# design.net
KiCad netlist of a schematic drawn in Altium Designer
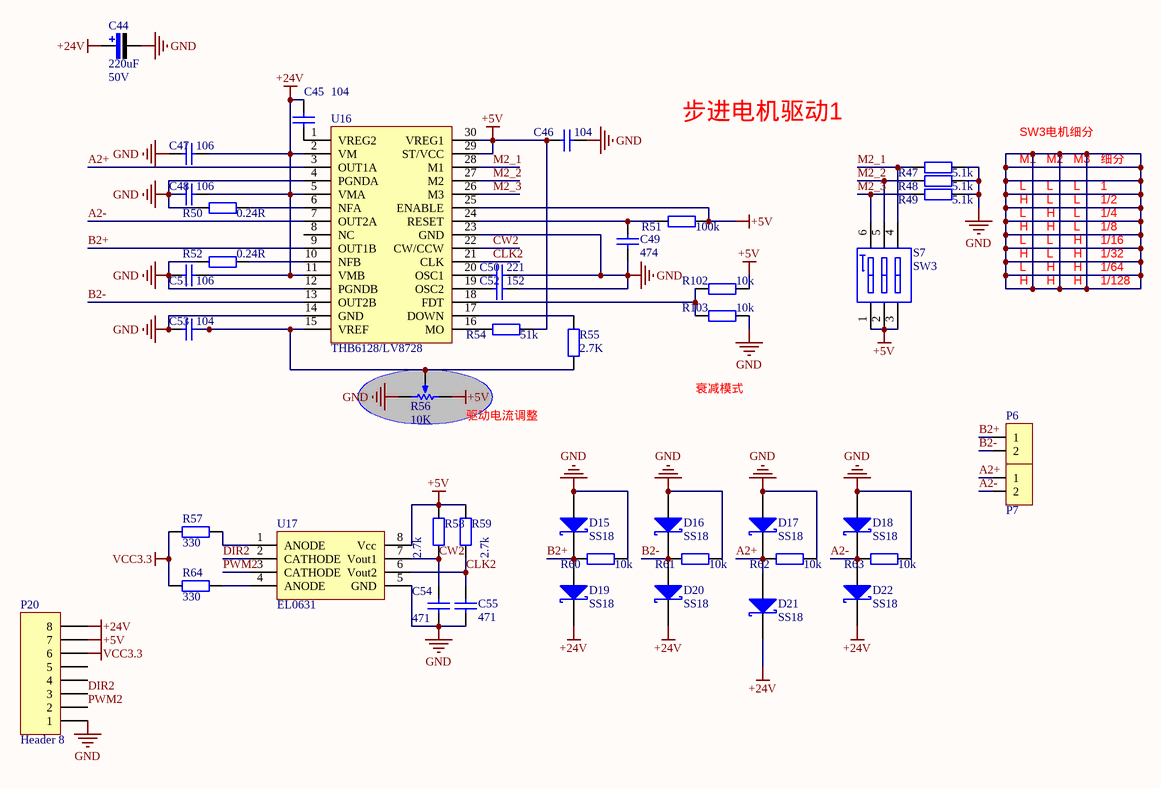
[diagram p0: 升降电机驱动.SchDoc]

(export (version "E")
  (design (tool "Eeschema 10.0.6"))
  (components
    (comp (ref "C44")
      (value "220uF")
      (footprint "C-RB-S10")
      (description "极性电解电容")
      (fields
        (field (name "VOL") "50V")
        (field (name "Comment") "Cap Pol")
        (field (name "PUBLISHER") "Altium Limited")
      )
      (libsource (lib "Fszhang") (part "Cap Pol"))
    )
    (comp (ref "C45")
      (value "104")
      (footprint "C-RAD-0603")
      (description "无极性电容")
      (fields (field (name "Comment") "Cap") (field (name "PUBLISHER") "Altium Limited"))
      (libsource (lib "Fszhang") (part "Cap"))
    )
    (comp (ref "C46")
      (value "104")
      (footprint "C-RAD-0603")
      (description "无极性电容")
      (fields (field (name "Comment") "Cap") (field (name "PUBLISHER") "Altium Limited"))
      (libsource (lib "Fszhang") (part "Cap"))
    )
    (comp (ref "C47")
      (value "106")
      (footprint "C-RAD-0603")
      (description "无极性电容")
      (fields (field (name "Comment") "Cap") (field (name "PUBLISHER") "Altium Limited"))
      (libsource (lib "Fszhang") (part "Cap"))
    )
    (comp (ref "C48")
      (value "106")
      (footprint "C-RAD-0603")
      (description "无极性电容")
      (fields (field (name "Comment") "Cap") (field (name "PUBLISHER") "Altium Limited"))
      (libsource (lib "Fszhang") (part "Cap"))
    )
    (comp (ref "C49")
      (value "474")
      (footprint "C-RAD-0603")
      (description "无极性电容")
      (fields (field (name "Comment") "Cap") (field (name "PUBLISHER") "Altium Limited"))
      (libsource (lib "Fszhang") (part "Cap"))
    )
    (comp (ref "C50")
      (value "221")
      (footprint "C-RAD-0603")
      (description "无极性电容")
      (fields (field (name "Comment") "Cap") (field (name "PUBLISHER") "Altium Limited"))
      (libsource (lib "Fszhang") (part "Cap"))
    )
    (comp (ref "C51")
      (value "106")
      (footprint "C-RAD-0603")
      (description "无极性电容")
      (fields (field (name "Comment") "Cap") (field (name "PUBLISHER") "Altium Limited"))
      (libsource (lib "Fszhang") (part "Cap"))
    )
    (comp (ref "C52")
      (value "152")
      (footprint "C-RAD-0603")
      (description "无极性电容")
      (fields (field (name "Comment") "Cap") (field (name "PUBLISHER") "Altium Limited"))
      (libsource (lib "Fszhang") (part "Cap"))
    )
    (comp (ref "C53")
      (value "104")
      (footprint "C-RAD-0603")
      (description "无极性电容")
      (fields (field (name "Comment") "Cap") (field (name "PUBLISHER") "Altium Limited"))
      (libsource (lib "Fszhang") (part "Cap"))
    )
    (comp (ref "C54")
      (value "471")
      (footprint "C-RAD-0603")
      (description "无极性电容")
      (fields (field (name "Comment") "Cap") (field (name "PUBLISHER") "Altium Limited"))
      (libsource (lib "Fszhang") (part "Cap"))
    )
    (comp (ref "C55")
      (value "471")
      (footprint "C-RAD-0603")
      (description "无极性电容")
      (fields (field (name "Comment") "Cap") (field (name "PUBLISHER") "Altium Limited"))
      (libsource (lib "Fszhang") (part "Cap"))
    )
    (comp (ref "D15")
      (value "D-Schottky")
      (footprint "DIODE-SMA")
      (description "肖特基二极管")
      (fields (field (name "TYPE") "SS18") (field (name "PUBLISHER") "Altium Limited"))
      (libsource (lib "Fszhang") (part "D-Schottky"))
    )
    (comp (ref "D16")
      (value "D-Schottky")
      (footprint "DIODE-SMA")
      (description "肖特基二极管")
      (fields (field (name "TYPE") "SS18") (field (name "PUBLISHER") "Altium Limited"))
      (libsource (lib "Fszhang") (part "D-Schottky"))
    )
    (comp (ref "D17")
      (value "D-Schottky")
      (footprint "DIODE-SMA")
      (description "肖特基二极管")
      (fields (field (name "TYPE") "SS18") (field (name "PUBLISHER") "Altium Limited"))
      (libsource (lib "Fszhang") (part "D-Schottky"))
    )
    (comp (ref "D18")
      (value "D-Schottky")
      (footprint "DIODE-SMA")
      (description "肖特基二极管")
      (fields (field (name "TYPE") "SS18") (field (name "PUBLISHER") "Altium Limited"))
      (libsource (lib "Fszhang") (part "D-Schottky"))
    )
    (comp (ref "D19")
      (value "D-Schottky")
      (footprint "DIODE-SMA")
      (description "肖特基二极管")
      (fields (field (name "TYPE") "SS18") (field (name "PUBLISHER") "Altium Limited"))
      (libsource (lib "Fszhang") (part "D-Schottky"))
    )
    (comp (ref "D20")
      (value "D-Schottky")
      (footprint "DIODE-SMA")
      (description "肖特基二极管")
      (fields (field (name "TYPE") "SS18") (field (name "PUBLISHER") "Altium Limited"))
      (libsource (lib "Fszhang") (part "D-Schottky"))
    )
    (comp (ref "D21")
      (value "D-Schottky")
      (footprint "DIODE-SMA")
      (description "肖特基二极管")
      (fields (field (name "TYPE") "SS18") (field (name "PUBLISHER") "Altium Limited"))
      (libsource (lib "Fszhang") (part "D-Schottky"))
    )
    (comp (ref "D22")
      (value "D-Schottky")
      (footprint "DIODE-SMA")
      (description "肖特基二极管")
      (fields (field (name "TYPE") "SS18") (field (name "PUBLISHER") "Altium Limited"))
      (libsource (lib "Fszhang") (part "D-Schottky"))
    )
    (comp (ref "P6") (value "cnt2p") (footprint "接线端子5mm间距2p") (libsource (lib "MY_Library") (part "cnt2p")))
    (comp (ref "P7") (value "cnt2p") (footprint "接线端子5mm间距2p") (libsource (lib "MY_Library") (part "cnt2p")))
    (comp (ref "P20")
      (value "Header 8")
      (footprint "PH2.0-8P")
      (description "Header, 8-Pin")
      (fields (field (name "PUBLISHER") "Altium Limited"))
      (libsource (lib "Fszhang") (part "Header 8"))
    )
    (comp (ref "R47")
      (value "5.1k")
      (footprint "0603-1")
      (description "贴片电阻")
      (fields (field (name "Comment") "Res1") (field (name "PUBLISHER") "Altium Limited"))
      (libsource (lib "Fszhang") (part "Res1"))
    )
    (comp (ref "R48")
      (value "5.1k")
      (footprint "0603-1")
      (description "贴片电阻")
      (fields (field (name "Comment") "Res1") (field (name "PUBLISHER") "Altium Limited"))
      (libsource (lib "Fszhang") (part "Res1"))
    )
    (comp (ref "R49")
      (value "5.1k")
      (footprint "0603-1")
      (description "贴片电阻")
      (fields (field (name "Comment") "Res1") (field (name "PUBLISHER") "Altium Limited"))
      (libsource (lib "Fszhang") (part "Res1"))
    )
    (comp (ref "R50")
      (value "0.24R")
      (footprint "2512")
      (description "贴片电阻")
      (fields (field (name "Comment") "Res1") (field (name "PUBLISHER") "Altium Limited"))
      (libsource (lib "Fszhang") (part "Res1"))
    )
    (comp (ref "R51")
      (value "100k")
      (footprint "0603-1")
      (description "贴片电阻")
      (fields (field (name "Comment") "Res1") (field (name "PUBLISHER") "Altium Limited"))
      (libsource (lib "Fszhang") (part "Res1"))
    )
    (comp (ref "R52")
      (value "0.24R")
      (footprint "2512")
      (description "贴片电阻")
      (fields (field (name "Comment") "Res1") (field (name "PUBLISHER") "Altium Limited"))
      (libsource (lib "") (part "Res1_2"))
    )
    (comp (ref "R54")
      (value "51k")
      (footprint "0603-1")
      (description "贴片电阻")
      (fields (field (name "Comment") "Res1") (field (name "PUBLISHER") "Altium Limited"))
      (libsource (lib "Fszhang") (part "Res1"))
    )
    (comp (ref "R55")
      (value "2.7K")
      (footprint "0603-1")
      (description "贴片电阻")
      (fields (field (name "Comment") "Res1") (field (name "PUBLISHER") "Altium Limited"))
      (libsource (lib "") (part "Res1_3"))
    )
    (comp (ref "R56")
      (value "10K")
      (footprint "VR-3266W")
      (description "精密可调电阻")
      (fields (field (name "Comment") "RPot") (field (name "PUBLISHER") "Altium Limited"))
      (libsource (lib "Fszhang") (part "RPot"))
    )
    (comp (ref "R57")
      (value "330")
      (footprint "0603-1")
      (description "贴片电阻")
      (fields (field (name "Comment") "Res1") (field (name "PUBLISHER") "Altium Limited"))
      (libsource (lib "") (part "Res1_2"))
    )
    (comp (ref "R58")
      (value "2.7k")
      (footprint "0603-1")
      (description "贴片电阻")
      (fields (field (name "Comment") "Res1") (field (name "PUBLISHER") "Altium Limited"))
      (libsource (lib "") (part "Res1_1"))
    )
    (comp (ref "R59")
      (value "2.7k")
      (footprint "0603-1")
      (description "贴片电阻")
      (fields (field (name "Comment") "Res1") (field (name "PUBLISHER") "Altium Limited"))
      (libsource (lib "") (part "Res1_1"))
    )
    (comp (ref "R60")
      (value "10k")
      (footprint "0603-1")
      (description "贴片电阻")
      (fields (field (name "Comment") "Res1") (field (name "PUBLISHER") "Altium Limited"))
      (libsource (lib "Fszhang") (part "Res1"))
    )
    (comp (ref "R61")
      (value "10k")
      (footprint "0603-1")
      (description "贴片电阻")
      (fields (field (name "Comment") "Res1") (field (name "PUBLISHER") "Altium Limited"))
      (libsource (lib "Fszhang") (part "Res1"))
    )
    (comp (ref "R62")
      (value "10k")
      (footprint "0603-1")
      (description "贴片电阻")
      (fields (field (name "Comment") "Res1") (field (name "PUBLISHER") "Altium Limited"))
      (libsource (lib "Fszhang") (part "Res1"))
    )
    (comp (ref "R63")
      (value "10k")
      (footprint "0603-1")
      (description "贴片电阻")
      (fields (field (name "Comment") "Res1") (field (name "PUBLISHER") "Altium Limited"))
      (libsource (lib "Fszhang") (part "Res1"))
    )
    (comp (ref "R64")
      (value "330")
      (footprint "0603-1")
      (description "贴片电阻")
      (fields (field (name "Comment") "Res1") (field (name "PUBLISHER") "Altium Limited"))
      (libsource (lib "") (part "Res1_2"))
    )
    (comp (ref "R102")
      (value "10k")
      (footprint "0603-1")
      (description "贴片电阻")
      (fields (field (name "Comment") "Res1") (field (name "PUBLISHER") "Altium Limited"))
      (libsource (lib "Fszhang") (part "Res1"))
    )
    (comp (ref "R103")
      (value "10k")
      (footprint "0603-1")
      (description "贴片电阻")
      (fields (field (name "Comment") "Res1") (field (name "PUBLISHER") "Altium Limited"))
      (libsource (lib "Fszhang") (part "Res1"))
    )
    (comp (ref "S7")
      (value "SW3")
      (footprint "SW6_3BIT")
      (description "3位编码开关")
      (libsource (lib "Fszhang") (part "SW3"))
    )
    (comp (ref "U16")
      (value "THB6128/LV8728")
      (footprint "SIOC-30-W")
      (description "步进电机驱动")
      (libsource (lib "Fszhang") (part "THB6128"))
    )
    (comp (ref "U17")
      (value "EL0631")
      (footprint "EL0631")
      (description "双路隔离光耦")
      (libsource (lib "Fszhang") (part "EL0631"))
    )
  )
  (nets
    (net (code "1") (name "+5V") (class "Default")
      (node (ref "C46") (pin "1") (pinfunction "1_1") (pintype "passive"))
      (node (ref "P20") (pin "7") (pinfunction "7_7") (pintype "passive"))
      (node (ref "R102") (pin "2") (pinfunction "2_2") (pintype "passive"))
      (node (ref "R51") (pin "2") (pinfunction "2_2") (pintype "passive"))
      (node (ref "R54") (pin "2") (pinfunction "2_2") (pintype "passive"))
      (node (ref "R56") (pin "1") (pinfunction "TOP_1") (pintype "passive"))
      (node (ref "R58") (pin "2") (pinfunction "2_2") (pintype "passive"))
      (node (ref "R59") (pin "2") (pinfunction "2_2") (pintype "passive"))
      (node (ref "S7") (pin "1") (pinfunction "1_1") (pintype "passive"))
      (node (ref "S7") (pin "2") (pinfunction "2_2") (pintype "passive"))
      (node (ref "S7") (pin "3") (pinfunction "3_3") (pintype "passive"))
      (node (ref "U16") (pin "25") (pinfunction "ENABLE_25") (pintype "passive"))
      (node (ref "U16") (pin "29") (pinfunction "ST/VCC_29") (pintype "passive"))
      (node (ref "U16") (pin "30") (pinfunction "VREG1_30") (pintype "passive"))
      (node (ref "U17") (pin "8") (pinfunction "Vcc_8") (pintype "passive"))
    )
    (net (code "2") (name "+24V") (class "Default")
      (node (ref "C44") (pin "1") (pinfunction "1_1") (pintype "passive"))
      (node (ref "C45") (pin "1") (pinfunction "1_1") (pintype "passive"))
      (node (ref "C47") (pin "2") (pinfunction "2_2") (pintype "passive"))
      (node (ref "C48") (pin "2") (pinfunction "2_2") (pintype "passive"))
      (node (ref "C51") (pin "2") (pinfunction "2_2") (pintype "passive"))
      (node (ref "D19") (pin "2") (pinfunction "K_2") (pintype "passive"))
      (node (ref "D20") (pin "2") (pinfunction "K_2") (pintype "passive"))
      (node (ref "D21") (pin "2") (pinfunction "K_2") (pintype "passive"))
      (node (ref "D22") (pin "2") (pinfunction "K_2") (pintype "passive"))
      (node (ref "P20") (pin "8") (pinfunction "8_8") (pintype "passive"))
      (node (ref "U16") (pin "11") (pinfunction "VMB_11") (pintype "passive"))
      (node (ref "U16") (pin "2") (pinfunction "VM_2") (pintype "passive"))
      (node (ref "U16") (pin "5") (pinfunction "VMA_5") (pintype "passive"))
    )
    (net (code "3") (name "/A2+") (class "Default")
      (node (ref "D17") (pin "2") (pinfunction "K_2") (pintype "passive"))
      (node (ref "D21") (pin "1") (pinfunction "A_1") (pintype "passive"))
      (node (ref "P7") (pin "1") (pinfunction "1_1") (pintype "passive"))
      (node (ref "R62") (pin "1") (pinfunction "1_1") (pintype "passive"))
      (node (ref "U16") (pin "3") (pinfunction "OUT1A_3") (pintype "passive"))
    )
    (net (code "4") (name "/A2-") (class "Default")
      (node (ref "D18") (pin "2") (pinfunction "K_2") (pintype "passive"))
      (node (ref "D22") (pin "1") (pinfunction "A_1") (pintype "passive"))
      (node (ref "P7") (pin "2") (pinfunction "2_2") (pintype "passive"))
      (node (ref "R63") (pin "1") (pinfunction "1_1") (pintype "passive"))
      (node (ref "U16") (pin "7") (pinfunction "OUT2A_7") (pintype "passive"))
    )
    (net (code "5") (name "/B2+") (class "Default")
      (node (ref "D15") (pin "2") (pinfunction "K_2") (pintype "passive"))
      (node (ref "D19") (pin "1") (pinfunction "A_1") (pintype "passive"))
      (node (ref "P6") (pin "1") (pinfunction "1_1") (pintype "passive"))
      (node (ref "R60") (pin "1") (pinfunction "1_1") (pintype "passive"))
      (node (ref "U16") (pin "9") (pinfunction "OUT1B_9") (pintype "passive"))
    )
    (net (code "6") (name "/B2-") (class "Default")
      (node (ref "D16") (pin "2") (pinfunction "K_2") (pintype "passive"))
      (node (ref "D20") (pin "1") (pinfunction "A_1") (pintype "passive"))
      (node (ref "P6") (pin "2") (pinfunction "2_2") (pintype "passive"))
      (node (ref "R61") (pin "1") (pinfunction "1_1") (pintype "passive"))
      (node (ref "U16") (pin "13") (pinfunction "OUT2B_13") (pintype "passive"))
    )
    (net (code "7") (name "/CLK2") (class "Default")
      (node (ref "C55") (pin "2") (pinfunction "2_2") (pintype "passive"))
      (node (ref "R59") (pin "1") (pinfunction "1_1") (pintype "passive"))
      (node (ref "U16") (pin "21") (pinfunction "CLK_21") (pintype "passive"))
      (node (ref "U17") (pin "6") (pinfunction "Vout2_6") (pintype "passive"))
    )
    (net (code "8") (name "/CW2") (class "Default")
      (node (ref "C54") (pin "2") (pinfunction "2_2") (pintype "passive"))
      (node (ref "R58") (pin "1") (pinfunction "1_1") (pintype "passive"))
      (node (ref "U16") (pin "22") (pinfunction "CW/CCW_22") (pintype "passive"))
      (node (ref "U17") (pin "7") (pinfunction "Vout1_7") (pintype "passive"))
    )
    (net (code "9") (name "/DIR2") (class "Default")
      (node (ref "P20") (pin "3") (pinfunction "3_3") (pintype "passive"))
      (node (ref "U17") (pin "2") (pinfunction "CATHODE_2") (pintype "passive"))
    )
    (net (code "10") (name "/M2_1") (class "Default")
      (node (ref "R47") (pin "1") (pinfunction "1_1") (pintype "passive"))
      (node (ref "S7") (pin "4") (pinfunction "4_4") (pintype "passive"))
      (node (ref "U16") (pin "28") (pinfunction "M1_28") (pintype "passive"))
    )
    (net (code "11") (name "/M2_2") (class "Default")
      (node (ref "R48") (pin "1") (pinfunction "1_1") (pintype "passive"))
      (node (ref "S7") (pin "5") (pinfunction "5_5") (pintype "passive"))
      (node (ref "U16") (pin "27") (pinfunction "M2_27") (pintype "passive"))
    )
    (net (code "12") (name "/M2_3") (class "Default")
      (node (ref "R49") (pin "1") (pinfunction "1_1") (pintype "passive"))
      (node (ref "S7") (pin "6") (pinfunction "6_6") (pintype "passive"))
      (node (ref "U16") (pin "26") (pinfunction "M3_26") (pintype "passive"))
    )
    (net (code "13") (name "/PWM2") (class "Default")
      (node (ref "P20") (pin "2") (pinfunction "2_2") (pintype "passive"))
      (node (ref "U17") (pin "3") (pinfunction "CATHODE_3") (pintype "passive"))
    )
    (net (code "14") (name "GND") (class "Default")
      (node (ref "C44") (pin "2") (pinfunction "2_2") (pintype "passive"))
      (node (ref "C46") (pin "2") (pinfunction "2_2") (pintype "passive"))
      (node (ref "C47") (pin "1") (pinfunction "1_1") (pintype "passive"))
      (node (ref "C48") (pin "1") (pinfunction "1_1") (pintype "passive"))
      (node (ref "C49") (pin "1") (pinfunction "1_1") (pintype "passive"))
      (node (ref "C50") (pin "2") (pinfunction "2_2") (pintype "passive"))
      (node (ref "C51") (pin "1") (pinfunction "1_1") (pintype "passive"))
      (node (ref "C52") (pin "2") (pinfunction "2_2") (pintype "passive"))
      (node (ref "C53") (pin "1") (pinfunction "1_1") (pintype "passive"))
      (node (ref "C54") (pin "1") (pinfunction "1_1") (pintype "passive"))
      (node (ref "C55") (pin "1") (pinfunction "1_1") (pintype "passive"))
      (node (ref "D15") (pin "1") (pinfunction "A_1") (pintype "passive"))
      (node (ref "D16") (pin "1") (pinfunction "A_1") (pintype "passive"))
      (node (ref "D17") (pin "1") (pinfunction "A_1") (pintype "passive"))
      (node (ref "D18") (pin "1") (pinfunction "A_1") (pintype "passive"))
      (node (ref "P20") (pin "1") (pinfunction "1_1") (pintype "passive"))
      (node (ref "R103") (pin "2") (pinfunction "2_2") (pintype "passive"))
      (node (ref "R47") (pin "2") (pinfunction "2_2") (pintype "passive"))
      (node (ref "R48") (pin "2") (pinfunction "2_2") (pintype "passive"))
      (node (ref "R49") (pin "2") (pinfunction "2_2") (pintype "passive"))
      (node (ref "R50") (pin "1") (pinfunction "1_1") (pintype "passive"))
      (node (ref "R52") (pin "2") (pinfunction "2_2") (pintype "passive"))
      (node (ref "R56") (pin "3") (pinfunction "BOT_3") (pintype "passive"))
      (node (ref "R60") (pin "2") (pinfunction "2_2") (pintype "passive"))
      (node (ref "R61") (pin "2") (pinfunction "2_2") (pintype "passive"))
      (node (ref "R62") (pin "2") (pinfunction "2_2") (pintype "passive"))
      (node (ref "R63") (pin "2") (pinfunction "2_2") (pintype "passive"))
      (node (ref "U16") (pin "12") (pinfunction "PGNDB_12") (pintype "passive"))
      (node (ref "U16") (pin "14") (pinfunction "GND_14") (pintype "passive"))
      (node (ref "U16") (pin "23") (pinfunction "GND_23") (pintype "passive"))
      (node (ref "U16") (pin "4") (pinfunction "PGNDA_4") (pintype "passive"))
      (node (ref "U17") (pin "5") (pinfunction "GND_5") (pintype "passive"))
    )
    (net (code "15") (name "Net-(R56-TAP)") (class "Default")
      (node (ref "C53") (pin "2") (pinfunction "2_2") (pintype "passive"))
      (node (ref "R55") (pin "2") (pinfunction "2_2") (pintype "passive"))
      (node (ref "R56") (pin "2") (pinfunction "TAP_2") (pintype "passive"))
      (node (ref "U16") (pin "15") (pinfunction "VREF_15") (pintype "passive"))
    )
    (net (code "16") (name "Net-(R57-Pad1)") (class "Default")
      (node (ref "R57") (pin "1") (pinfunction "1_1") (pintype "passive"))
      (node (ref "U17") (pin "1") (pinfunction "ANODE_1") (pintype "passive"))
    )
    (net (code "17") (name "Net-(R64-Pad1)") (class "Default")
      (node (ref "R64") (pin "1") (pinfunction "1_1") (pintype "passive"))
      (node (ref "U17") (pin "4") (pinfunction "ANODE_4") (pintype "passive"))
    )
    (net (code "18") (name "Net-(U16-DOWN)") (class "Default")
      (node (ref "R55") (pin "1") (pinfunction "1_1") (pintype "passive"))
      (node (ref "U16") (pin "17") (pinfunction "DOWN_17") (pintype "passive"))
    )
    (net (code "19") (name "Net-(U16-FDT)") (class "Default")
      (node (ref "R102") (pin "1") (pinfunction "1_1") (pintype "passive"))
      (node (ref "R103") (pin "1") (pinfunction "1_1") (pintype "passive"))
      (node (ref "U16") (pin "18") (pinfunction "FDT_18") (pintype "passive"))
    )
    (net (code "20") (name "Net-(U16-MO)") (class "Default")
      (node (ref "R54") (pin "1") (pinfunction "1_1") (pintype "passive"))
      (node (ref "U16") (pin "16") (pinfunction "MO_16") (pintype "passive"))
    )
    (net (code "21") (name "Net-(U16-NFA)") (class "Default")
      (node (ref "R50") (pin "2") (pinfunction "2_2") (pintype "passive"))
      (node (ref "U16") (pin "6") (pinfunction "NFA_6") (pintype "passive"))
    )
    (net (code "22") (name "Net-(U16-NFB)") (class "Default")
      (node (ref "R52") (pin "1") (pinfunction "1_1") (pintype "passive"))
      (node (ref "U16") (pin "10") (pinfunction "NFB_10") (pintype "passive"))
    )
    (net (code "23") (name "Net-(U16-OSC1)") (class "Default")
      (node (ref "C50") (pin "1") (pinfunction "1_1") (pintype "passive"))
      (node (ref "U16") (pin "20") (pinfunction "OSC1_20") (pintype "passive"))
    )
    (net (code "24") (name "Net-(U16-OSC2)") (class "Default")
      (node (ref "C52") (pin "1") (pinfunction "1_1") (pintype "passive"))
      (node (ref "U16") (pin "19") (pinfunction "OSC2_19") (pintype "passive"))
    )
    (net (code "25") (name "Net-(U16-RESET)") (class "Default")
      (node (ref "C49") (pin "2") (pinfunction "2_2") (pintype "passive"))
      (node (ref "R51") (pin "1") (pinfunction "1_1") (pintype "passive"))
      (node (ref "U16") (pin "24") (pinfunction "RESET_24") (pintype "passive"))
    )
    (net (code "26") (name "Net-(U16-VREG2)") (class "Default")
      (node (ref "C45") (pin "2") (pinfunction "2_2") (pintype "passive"))
      (node (ref "U16") (pin "1") (pinfunction "VREG2_1") (pintype "passive"))
    )
    (net (code "27") (name "VCC3.3") (class "Default")
      (node (ref "P20") (pin "6") (pinfunction "6_6") (pintype "passive"))
      (node (ref "R57") (pin "2") (pinfunction "2_2") (pintype "passive"))
      (node (ref "R64") (pin "2") (pinfunction "2_2") (pintype "passive"))
    )
    (net (code "28") (name "unconnected-(P20-Pad4)") (class "Default")
      (node (ref "P20") (pin "4") (pinfunction "4_4") (pintype "passive"))
    )
    (net (code "29") (name "unconnected-(P20-Pad5)") (class "Default")
      (node (ref "P20") (pin "5") (pinfunction "5_5") (pintype "passive"))
    )
    (net (code "30") (name "unconnected-(U16-NC-Pad8)") (class "Default")
      (node (ref "U16") (pin "8") (pinfunction "NC_8") (pintype "passive"))
    )
  )
)
